# dc_sensor_v2.net
KiCad netlist of a schematic drawn in EAGLE
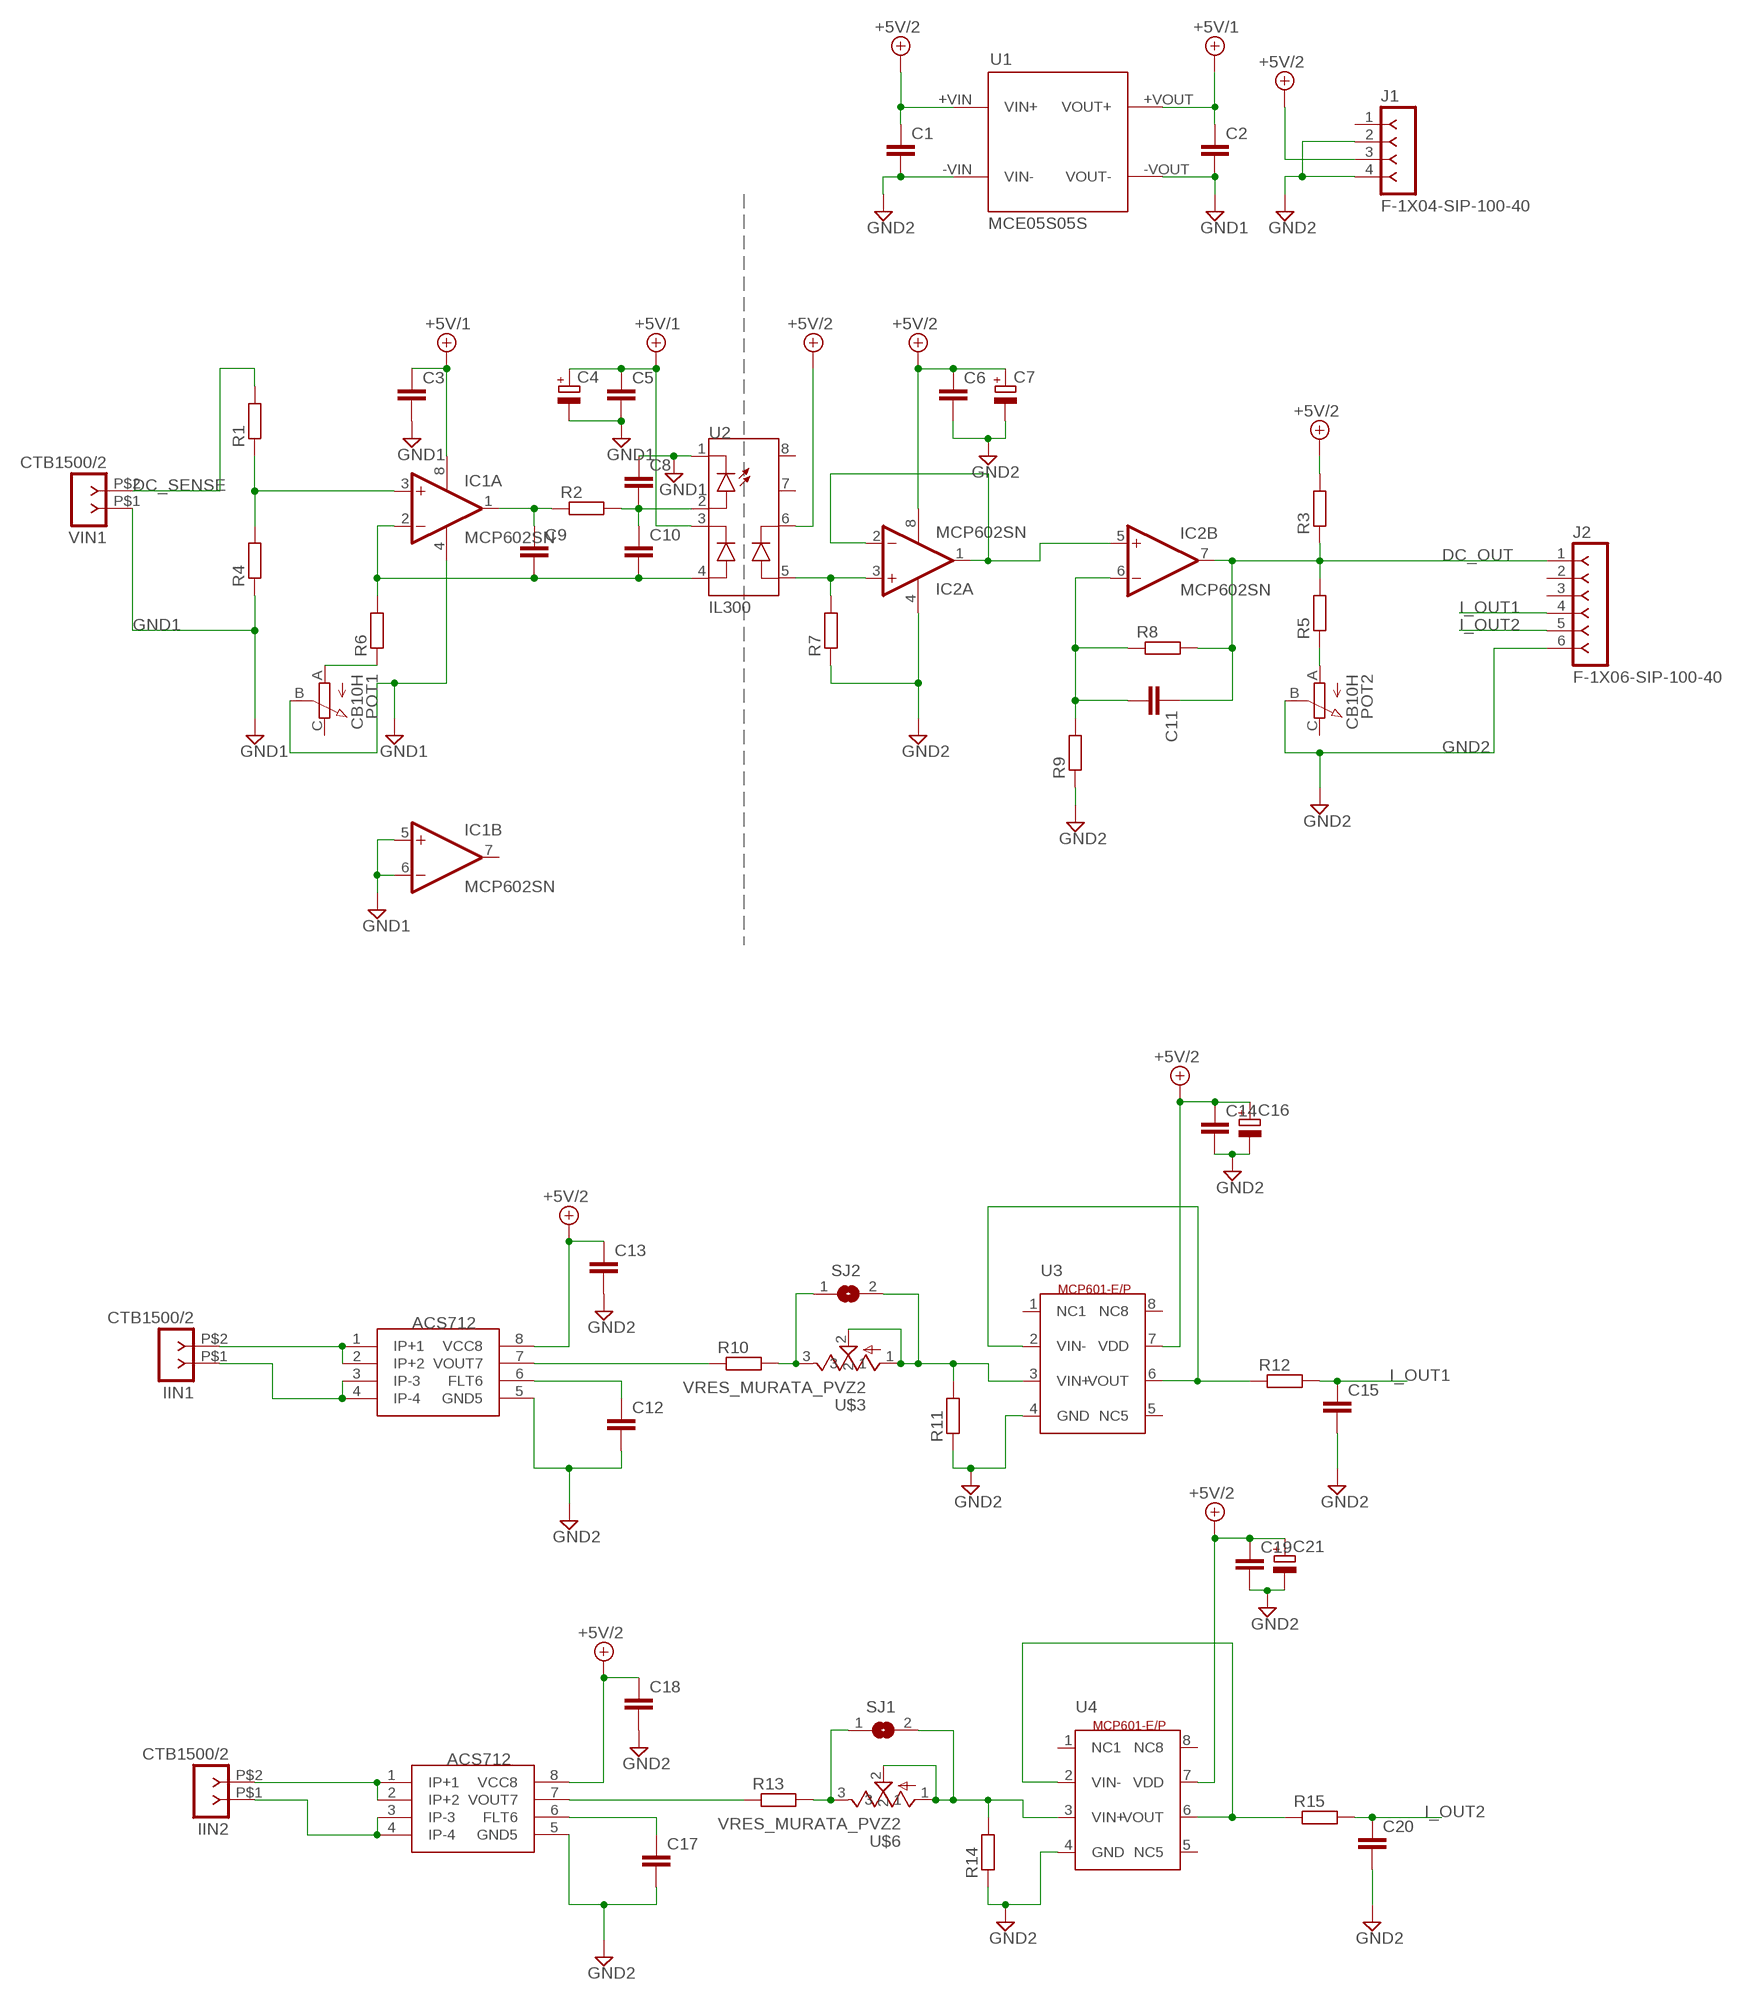
[diagram p0: schematic, sheet 1]

(export (version "E")
  (design (tool "Eeschema 10.0.6"))
  (components
    (comp (ref "C1")
      (value "C-EUC1206")
      (footprint "eagle-import:C1206")
      (libsource (lib "eagle-import") (part "C-EUC1206"))
    )
    (comp (ref "C2")
      (value "C-EUC1206")
      (footprint "eagle-import:C1206")
      (libsource (lib "eagle-import") (part "C-EUC1206"))
    )
    (comp (ref "C3")
      (value "C-EU025-040X050")
      (footprint "eagle-import:C025-040X050")
      (libsource (lib "eagle-import") (part "C-EU025-040X050"))
    )
    (comp (ref "C4")
      (value "CPOL-EUE2-5")
      (footprint "eagle-import:E2-5")
      (libsource (lib "eagle-import") (part "CPOL-EUE2-5"))
    )
    (comp (ref "C5")
      (value "C-EU025-040X050")
      (footprint "eagle-import:C025-040X050")
      (libsource (lib "eagle-import") (part "C-EU025-040X050"))
    )
    (comp (ref "C6")
      (value "C-EU025-040X050")
      (footprint "eagle-import:C025-040X050")
      (libsource (lib "eagle-import") (part "C-EU025-040X050"))
    )
    (comp (ref "C7")
      (value "CPOL-EUE2-5")
      (footprint "eagle-import:E2-5")
      (libsource (lib "eagle-import") (part "CPOL-EUE2-5"))
    )
    (comp (ref "C8")
      (value "C-EU025-040X050")
      (footprint "eagle-import:C025-040X050")
      (libsource (lib "eagle-import") (part "C-EU025-040X050"))
    )
    (comp (ref "C9")
      (value "C-EU025-040X050")
      (footprint "eagle-import:C025-040X050")
      (libsource (lib "eagle-import") (part "C-EU025-040X050"))
    )
    (comp (ref "C10")
      (value "C-EU025-040X050")
      (footprint "eagle-import:C025-040X050")
      (libsource (lib "eagle-import") (part "C-EU025-040X050"))
    )
    (comp (ref "C11")
      (value "C-EU025-040X050")
      (footprint "eagle-import:C025-040X050")
      (libsource (lib "eagle-import") (part "C-EU025-040X050"))
    )
    (comp (ref "C12")
      (value "C-EU025-030X050")
      (footprint "eagle-import:C025-030X050")
      (libsource (lib "eagle-import") (part "C-EU025-030X050"))
    )
    (comp (ref "C13")
      (value "C-EUC0603")
      (footprint "eagle-import:C0603")
      (libsource (lib "eagle-import") (part "C-EUC0603"))
    )
    (comp (ref "C14")
      (value "C-EUC0603")
      (footprint "eagle-import:C0603")
      (libsource (lib "eagle-import") (part "C-EUC0603"))
    )
    (comp (ref "C15")
      (value "C-EU025-030X050")
      (footprint "eagle-import:C025-030X050")
      (libsource (lib "eagle-import") (part "C-EU025-030X050"))
    )
    (comp (ref "C16")
      (value "CPOL-EUE2.5-6")
      (footprint "eagle-import:E2,5-6")
      (libsource (lib "eagle-import") (part "CPOL-EUE2.5-6"))
    )
    (comp (ref "C17")
      (value "C-EU025-030X050")
      (footprint "eagle-import:C025-030X050")
      (libsource (lib "eagle-import") (part "C-EU025-030X050"))
    )
    (comp (ref "C18")
      (value "C-EUC0603")
      (footprint "eagle-import:C0603")
      (libsource (lib "eagle-import") (part "C-EUC0603"))
    )
    (comp (ref "C19")
      (value "C-EUC0603")
      (footprint "eagle-import:C0603")
      (libsource (lib "eagle-import") (part "C-EUC0603"))
    )
    (comp (ref "C20")
      (value "C-EU025-030X050")
      (footprint "eagle-import:C025-030X050")
      (libsource (lib "eagle-import") (part "C-EU025-030X050"))
    )
    (comp (ref "C21")
      (value "CPOL-EUE2.5-6")
      (footprint "eagle-import:E2,5-6")
      (libsource (lib "eagle-import") (part "CPOL-EUE2.5-6"))
    )
    (comp (ref "IC1")
      (value "MCP602SN")
      (footprint "eagle-import:SO08")
      (libsource (lib "eagle-import") (part "MCP602SN"))
    )
    (comp (ref "IC2")
      (value "MCP602SN")
      (footprint "eagle-import:SO08")
      (libsource (lib "eagle-import") (part "MCP602SN"))
    )
    (comp (ref "IIN1")
      (value "CTB1500/2")
      (footprint "eagle-import:CTB1500-2")
      (libsource (lib "eagle-import") (part "CTB1500/2"))
    )
    (comp (ref "IIN2")
      (value "CTB1500/2")
      (footprint "eagle-import:CTB1500-2")
      (libsource (lib "eagle-import") (part "CTB1500/2"))
    )
    (comp (ref "J1")
      (value "F-1X04-SIP-100-40")
      (footprint "eagle-import:SIP-100-04-40")
      (libsource (lib "eagle-import") (part "F-1X04-SIP-100-40"))
    )
    (comp (ref "J2")
      (value "F-1X06-SIP-100-40")
      (footprint "eagle-import:SIP-100-06-40")
      (libsource (lib "eagle-import") (part "F-1X06-SIP-100-40"))
    )
    (comp (ref "POT1")
      (value "CB10H")
      (footprint "eagle-import:CB10V")
      (libsource (lib "eagle-import") (part "CB10H"))
    )
    (comp (ref "POT2")
      (value "CB10H")
      (footprint "eagle-import:CB10V")
      (libsource (lib "eagle-import") (part "CB10H"))
    )
    (comp (ref "R1")
      (value "R-EU_0207/10")
      (footprint "eagle-import:0207_10")
      (libsource (lib "eagle-import") (part "R-EU_0207/10"))
    )
    (comp (ref "R2")
      (value "R-EU_0207/10")
      (footprint "eagle-import:0207_10")
      (libsource (lib "eagle-import") (part "R-EU_0207/10"))
    )
    (comp (ref "R3")
      (value "R-EU_0207/10")
      (footprint "eagle-import:0207_10")
      (libsource (lib "eagle-import") (part "R-EU_0207/10"))
    )
    (comp (ref "R4")
      (value "R-EU_0207/10")
      (footprint "eagle-import:0207_10")
      (libsource (lib "eagle-import") (part "R-EU_0207/10"))
    )
    (comp (ref "R5")
      (value "R-EU_0207/10")
      (footprint "eagle-import:0207_10")
      (libsource (lib "eagle-import") (part "R-EU_0207/10"))
    )
    (comp (ref "R6")
      (value "R-EU_0207/10")
      (footprint "eagle-import:0207_10")
      (libsource (lib "eagle-import") (part "R-EU_0207/10"))
    )
    (comp (ref "R7")
      (value "R-EU_0207/10")
      (footprint "eagle-import:0207_10")
      (libsource (lib "eagle-import") (part "R-EU_0207/10"))
    )
    (comp (ref "R8")
      (value "R-EU_0207/10")
      (footprint "eagle-import:0207_10")
      (libsource (lib "eagle-import") (part "R-EU_0207/10"))
    )
    (comp (ref "R9")
      (value "R-EU_0207/10")
      (footprint "eagle-import:0207_10")
      (libsource (lib "eagle-import") (part "R-EU_0207/10"))
    )
    (comp (ref "R10")
      (value "R-EU_0207/10")
      (footprint "eagle-import:0207_10")
      (libsource (lib "eagle-import") (part "R-EU_0207/10"))
    )
    (comp (ref "R11")
      (value "R-EU_0207/10")
      (footprint "eagle-import:0207_10")
      (libsource (lib "eagle-import") (part "R-EU_0207/10"))
    )
    (comp (ref "R12")
      (value "R-EU_0207/10")
      (footprint "eagle-import:0207_10")
      (libsource (lib "eagle-import") (part "R-EU_0207/10"))
    )
    (comp (ref "R13")
      (value "R-EU_0207/10")
      (footprint "eagle-import:0207_10")
      (libsource (lib "eagle-import") (part "R-EU_0207/10"))
    )
    (comp (ref "R14")
      (value "R-EU_0207/10")
      (footprint "eagle-import:0207_10")
      (libsource (lib "eagle-import") (part "R-EU_0207/10"))
    )
    (comp (ref "R15")
      (value "R-EU_0207/10")
      (footprint "eagle-import:0207_10")
      (libsource (lib "eagle-import") (part "R-EU_0207/10"))
    )
    (comp (ref "SJ1") (value "SJ") (footprint "eagle-import:SJ") (libsource (lib "eagle-import") (part "SJ")))
    (comp (ref "SJ2") (value "SJ") (footprint "eagle-import:SJ") (libsource (lib "eagle-import") (part "SJ")))
    (comp (ref "U$3")
      (value "VRES_MURATA_PVZ2")
      (footprint "eagle-import:MURATA_PVZ2A")
      (libsource (lib "eagle-import") (part "VRES_MURATA_PVZ2"))
    )
    (comp (ref "U$6")
      (value "VRES_MURATA_PVZ2")
      (footprint "eagle-import:MURATA_PVZ2A")
      (libsource (lib "eagle-import") (part "VRES_MURATA_PVZ2"))
    )
    (comp (ref "U1")
      (value "MCE05S05S")
      (footprint "eagle-import:MCEXXSXXS_SIP")
      (libsource (lib "eagle-import") (part "MCE05S05S"))
    )
    (comp (ref "U2")
      (value "IL300")
      (footprint "eagle-import:DIL08")
      (libsource (lib "eagle-import") (part "IL300"))
    )
    (comp (ref "U3")
      (value "MCP601")
      (footprint "eagle-import:SO8")
      (libsource (lib "eagle-import") (part "MCP601"))
    )
    (comp (ref "U4")
      (value "MCP601")
      (footprint "eagle-import:SO8")
      (libsource (lib "eagle-import") (part "MCP601"))
    )
    (comp (ref "U5")
      (value "ACS712")
      (footprint "eagle-import:SO8")
      (libsource (lib "eagle-import") (part "ACS712"))
    )
    (comp (ref "U6")
      (value "ACS712")
      (footprint "eagle-import:SO8")
      (libsource (lib "eagle-import") (part "ACS712"))
    )
    (comp (ref "VIN1")
      (value "CTB1500/2")
      (footprint "eagle-import:CTB1500-2")
      (libsource (lib "eagle-import") (part "CTB1500/2"))
    )
  )
  (nets
    (net (code "1") (name "+5V{slash}1") (class "Default")
      (node (ref "C2") (pin "1") (pinfunction "1_1") (pintype "passive"))
      (node (ref "C3") (pin "1") (pinfunction "1_1") (pintype "passive"))
      (node (ref "C4") (pin "+") (pinfunction "+_+") (pintype "passive"))
      (node (ref "C5") (pin "1") (pinfunction "1_1") (pintype "passive"))
      (node (ref "IC1") (pin "8") (pinfunction "V+_8") (pintype "power_in"))
      (node (ref "U1") (pin "+VOUT") (pinfunction "VOUT+_+VOUT") (pintype "bidirectional"))
      (node (ref "U2") (pin "3") (pinfunction "C_FB_3") (pintype "passive"))
    )
    (net (code "2") (name "+5V{slash}2") (class "Default")
      (node (ref "C1") (pin "1") (pinfunction "1_1") (pintype "passive"))
      (node (ref "C13") (pin "1") (pinfunction "1_1") (pintype "passive"))
      (node (ref "C14") (pin "1") (pinfunction "1_1") (pintype "passive"))
      (node (ref "C16") (pin "+") (pinfunction "+_+") (pintype "passive"))
      (node (ref "C18") (pin "1") (pinfunction "1_1") (pintype "passive"))
      (node (ref "C19") (pin "1") (pinfunction "1_1") (pintype "passive"))
      (node (ref "C21") (pin "+") (pinfunction "+_+") (pintype "passive"))
      (node (ref "C6") (pin "1") (pinfunction "1_1") (pintype "passive"))
      (node (ref "C7") (pin "+") (pinfunction "+_+") (pintype "passive"))
      (node (ref "IC2") (pin "8") (pinfunction "V+_8") (pintype "power_in"))
      (node (ref "J1") (pin "3") (pinfunction "3_3") (pintype "passive"))
      (node (ref "R3") (pin "2") (pinfunction "2_2") (pintype "passive"))
      (node (ref "U1") (pin "+VIN") (pinfunction "VIN+_+VIN") (pintype "bidirectional"))
      (node (ref "U2") (pin "6") (pinfunction "C_OUT_6") (pintype "passive"))
      (node (ref "U3") (pin "7") (pinfunction "VDD_7") (pintype "power_in"))
      (node (ref "U4") (pin "7") (pinfunction "VDD_7") (pintype "power_in"))
      (node (ref "U5") (pin "8") (pinfunction "VCC8_8") (pintype "power_in"))
      (node (ref "U6") (pin "8") (pinfunction "VCC8_8") (pintype "power_in"))
    )
    (net (code "3") (name "/DC_OUT") (class "Default")
      (node (ref "C11") (pin "1") (pinfunction "1_1") (pintype "passive"))
      (node (ref "IC2") (pin "7") (pinfunction "OUT_7") (pintype "output"))
      (node (ref "J2") (pin "1") (pinfunction "1_1") (pintype "passive"))
      (node (ref "R3") (pin "1") (pinfunction "1_1") (pintype "passive"))
      (node (ref "R5") (pin "2") (pinfunction "2_2") (pintype "passive"))
      (node (ref "R8") (pin "2") (pinfunction "2_2") (pintype "passive"))
    )
    (net (code "4") (name "/DC_SENSE") (class "Default")
      (node (ref "R1") (pin "2") (pinfunction "2_2") (pintype "passive"))
      (node (ref "VIN1") (pin "P$2") (pinfunction "2_P$2") (pintype "passive"))
    )
    (net (code "5") (name "/I_OUT1") (class "Default")
      (node (ref "C15") (pin "1") (pinfunction "1_1") (pintype "passive"))
      (node (ref "J2") (pin "4") (pinfunction "4_4") (pintype "passive"))
      (node (ref "R12") (pin "2") (pinfunction "2_2") (pintype "passive"))
    )
    (net (code "6") (name "/I_OUT2") (class "Default")
      (node (ref "C20") (pin "1") (pinfunction "1_1") (pintype "passive"))
      (node (ref "J2") (pin "5") (pinfunction "5_5") (pintype "passive"))
      (node (ref "R15") (pin "2") (pinfunction "2_2") (pintype "passive"))
    )
    (net (code "7") (name "GND1") (class "Default")
      (node (ref "C2") (pin "2") (pinfunction "2_2") (pintype "passive"))
      (node (ref "C3") (pin "2") (pinfunction "2_2") (pintype "passive"))
      (node (ref "C4") (pin "-") (pinfunction "-_-") (pintype "passive"))
      (node (ref "C5") (pin "2") (pinfunction "2_2") (pintype "passive"))
      (node (ref "C8") (pin "1") (pinfunction "1_1") (pintype "passive"))
      (node (ref "IC1") (pin "4") (pinfunction "V-_4") (pintype "power_in"))
      (node (ref "IC1") (pin "5") (pinfunction "+IN_5") (pintype "input"))
      (node (ref "IC1") (pin "6") (pinfunction "-IN_6") (pintype "input"))
      (node (ref "POT1") (pin "B") (pinfunction "S_B") (pintype "passive"))
      (node (ref "R4") (pin "1") (pinfunction "1_1") (pintype "passive"))
      (node (ref "U1") (pin "-VOUT") (pinfunction "VOUT-_-VOUT") (pintype "bidirectional"))
      (node (ref "U2") (pin "1") (pinfunction "C_LED_1") (pintype "passive"))
      (node (ref "VIN1") (pin "P$1") (pinfunction "1_P$1") (pintype "passive"))
    )
    (net (code "8") (name "GND2") (class "Default")
      (node (ref "C1") (pin "2") (pinfunction "2_2") (pintype "passive"))
      (node (ref "C12") (pin "2") (pinfunction "2_2") (pintype "passive"))
      (node (ref "C13") (pin "2") (pinfunction "2_2") (pintype "passive"))
      (node (ref "C14") (pin "2") (pinfunction "2_2") (pintype "passive"))
      (node (ref "C15") (pin "2") (pinfunction "2_2") (pintype "passive"))
      (node (ref "C16") (pin "-") (pinfunction "-_-") (pintype "passive"))
      (node (ref "C17") (pin "2") (pinfunction "2_2") (pintype "passive"))
      (node (ref "C18") (pin "2") (pinfunction "2_2") (pintype "passive"))
      (node (ref "C19") (pin "2") (pinfunction "2_2") (pintype "passive"))
      (node (ref "C20") (pin "2") (pinfunction "2_2") (pintype "passive"))
      (node (ref "C21") (pin "-") (pinfunction "-_-") (pintype "passive"))
      (node (ref "C6") (pin "2") (pinfunction "2_2") (pintype "passive"))
      (node (ref "C7") (pin "-") (pinfunction "-_-") (pintype "passive"))
      (node (ref "IC2") (pin "4") (pinfunction "V-_4") (pintype "power_in"))
      (node (ref "J1") (pin "2") (pinfunction "2_2") (pintype "passive"))
      (node (ref "J1") (pin "4") (pinfunction "4_4") (pintype "passive"))
      (node (ref "J2") (pin "6") (pinfunction "6_6") (pintype "passive"))
      (node (ref "POT2") (pin "B") (pinfunction "S_B") (pintype "passive"))
      (node (ref "R11") (pin "1") (pinfunction "1_1") (pintype "passive"))
      (node (ref "R14") (pin "1") (pinfunction "1_1") (pintype "passive"))
      (node (ref "R7") (pin "1") (pinfunction "1_1") (pintype "passive"))
      (node (ref "R9") (pin "1") (pinfunction "1_1") (pintype "passive"))
      (node (ref "U1") (pin "-VIN") (pinfunction "VIN-_-VIN") (pintype "bidirectional"))
      (node (ref "U3") (pin "4") (pinfunction "GND_4") (pintype "power_in"))
      (node (ref "U4") (pin "4") (pinfunction "GND_4") (pintype "power_in"))
      (node (ref "U5") (pin "5") (pinfunction "GND5_5") (pintype "power_in"))
      (node (ref "U6") (pin "5") (pinfunction "GND5_5") (pintype "power_in"))
    )
    (net (code "9") (name "Net-(IC1A-+IN)") (class "Default")
      (node (ref "IC1") (pin "3") (pinfunction "+IN_3") (pintype "input"))
      (node (ref "R1") (pin "1") (pinfunction "1_1") (pintype "passive"))
      (node (ref "R4") (pin "2") (pinfunction "2_2") (pintype "passive"))
    )
    (net (code "10") (name "Net-(IC1A--IN)") (class "Default")
      (node (ref "C10") (pin "2") (pinfunction "2_2") (pintype "passive"))
      (node (ref "C9") (pin "2") (pinfunction "2_2") (pintype "passive"))
      (node (ref "IC1") (pin "2") (pinfunction "-IN_2") (pintype "input"))
      (node (ref "R6") (pin "2") (pinfunction "2_2") (pintype "passive"))
      (node (ref "U2") (pin "4") (pinfunction "A_FB_4") (pintype "passive"))
    )
    (net (code "11") (name "Net-(IC1A-OUT)") (class "Default")
      (node (ref "C9") (pin "1") (pinfunction "1_1") (pintype "passive"))
      (node (ref "IC1") (pin "1") (pinfunction "OUT_1") (pintype "output"))
      (node (ref "R2") (pin "1") (pinfunction "1_1") (pintype "passive"))
    )
    (net (code "12") (name "Net-(IC2A-+IN)") (class "Default")
      (node (ref "IC2") (pin "3") (pinfunction "+IN_3") (pintype "input"))
      (node (ref "R7") (pin "2") (pinfunction "2_2") (pintype "passive"))
      (node (ref "U2") (pin "5") (pinfunction "A_OUT_5") (pintype "passive"))
    )
    (net (code "13") (name "Net-(IC2A--IN)") (class "Default")
      (node (ref "IC2") (pin "1") (pinfunction "OUT_1") (pintype "output"))
      (node (ref "IC2") (pin "2") (pinfunction "-IN_2") (pintype "input"))
      (node (ref "IC2") (pin "5") (pinfunction "+IN_5") (pintype "input"))
    )
    (net (code "14") (name "Net-(IC2B--IN)") (class "Default")
      (node (ref "C11") (pin "2") (pinfunction "2_2") (pintype "passive"))
      (node (ref "IC2") (pin "6") (pinfunction "-IN_6") (pintype "input"))
      (node (ref "R8") (pin "1") (pinfunction "1_1") (pintype "passive"))
      (node (ref "R9") (pin "2") (pinfunction "2_2") (pintype "passive"))
    )
    (net (code "15") (name "Net-(IIN1-1)") (class "Default")
      (node (ref "IIN1") (pin "P$1") (pinfunction "1_P$1") (pintype "passive"))
      (node (ref "U6") (pin "3") (pinfunction "IP-3_3") (pintype "bidirectional"))
      (node (ref "U6") (pin "4") (pinfunction "IP-4_4") (pintype "bidirectional"))
    )
    (net (code "16") (name "Net-(IIN1-2)") (class "Default")
      (node (ref "IIN1") (pin "P$2") (pinfunction "2_P$2") (pintype "passive"))
      (node (ref "U6") (pin "1") (pinfunction "IP+1_1") (pintype "bidirectional"))
      (node (ref "U6") (pin "2") (pinfunction "IP+2_2") (pintype "bidirectional"))
    )
    (net (code "17") (name "Net-(IIN2-1)") (class "Default")
      (node (ref "IIN2") (pin "P$1") (pinfunction "1_P$1") (pintype "passive"))
      (node (ref "U5") (pin "3") (pinfunction "IP-3_3") (pintype "bidirectional"))
      (node (ref "U5") (pin "4") (pinfunction "IP-4_4") (pintype "bidirectional"))
    )
    (net (code "18") (name "Net-(IIN2-2)") (class "Default")
      (node (ref "IIN2") (pin "P$2") (pinfunction "2_P$2") (pintype "passive"))
      (node (ref "U5") (pin "1") (pinfunction "IP+1_1") (pintype "bidirectional"))
      (node (ref "U5") (pin "2") (pinfunction "IP+2_2") (pintype "bidirectional"))
    )
    (net (code "19") (name "Net-(POT1-PadA)") (class "Default")
      (node (ref "POT1") (pin "A") (pinfunction "A_A") (pintype "passive"))
      (node (ref "R6") (pin "1") (pinfunction "1_1") (pintype "passive"))
    )
    (net (code "20") (name "Net-(POT2-PadA)") (class "Default")
      (node (ref "POT2") (pin "A") (pinfunction "A_A") (pintype "passive"))
      (node (ref "R5") (pin "1") (pinfunction "1_1") (pintype "passive"))
    )
    (net (code "21") (name "Net-(R10-Pad2)") (class "Default")
      (node (ref "R10") (pin "2") (pinfunction "2_2") (pintype "passive"))
      (node (ref "SJ2") (pin "1") (pinfunction "1_1") (pintype "passive"))
      (node (ref "U$3") (pin "3") (pinfunction "3_3") (pintype "passive"))
    )
    (net (code "22") (name "Net-(R13-Pad2)") (class "Default")
      (node (ref "R13") (pin "2") (pinfunction "2_2") (pintype "passive"))
      (node (ref "SJ1") (pin "1") (pinfunction "1_1") (pintype "passive"))
      (node (ref "U$6") (pin "3") (pinfunction "3_3") (pintype "passive"))
    )
    (net (code "23") (name "Net-(U2-A_LED)") (class "Default")
      (node (ref "C10") (pin "1") (pinfunction "1_1") (pintype "passive"))
      (node (ref "C8") (pin "2") (pinfunction "2_2") (pintype "passive"))
      (node (ref "R2") (pin "2") (pinfunction "2_2") (pintype "passive"))
      (node (ref "U2") (pin "2") (pinfunction "A_LED_2") (pintype "passive"))
    )
    (net (code "24") (name "Net-(U3-VIN+)") (class "Default")
      (node (ref "R11") (pin "2") (pinfunction "2_2") (pintype "passive"))
      (node (ref "SJ2") (pin "2") (pinfunction "2_2") (pintype "passive"))
      (node (ref "U$3") (pin "1") (pinfunction "1_1") (pintype "passive"))
      (node (ref "U$3") (pin "2") (pinfunction "2_2") (pintype "passive"))
      (node (ref "U3") (pin "3") (pinfunction "VIN+_3") (pintype "bidirectional"))
    )
    (net (code "25") (name "Net-(U3-VIN-)") (class "Default")
      (node (ref "R12") (pin "1") (pinfunction "1_1") (pintype "passive"))
      (node (ref "U3") (pin "2") (pinfunction "VIN-_2") (pintype "bidirectional"))
      (node (ref "U3") (pin "6") (pinfunction "VOUT_6") (pintype "bidirectional"))
    )
    (net (code "26") (name "Net-(U4-VIN+)") (class "Default")
      (node (ref "R14") (pin "2") (pinfunction "2_2") (pintype "passive"))
      (node (ref "SJ1") (pin "2") (pinfunction "2_2") (pintype "passive"))
      (node (ref "U$6") (pin "1") (pinfunction "1_1") (pintype "passive"))
      (node (ref "U$6") (pin "2") (pinfunction "2_2") (pintype "passive"))
      (node (ref "U4") (pin "3") (pinfunction "VIN+_3") (pintype "bidirectional"))
    )
    (net (code "27") (name "Net-(U4-VIN-)") (class "Default")
      (node (ref "R15") (pin "1") (pinfunction "1_1") (pintype "passive"))
      (node (ref "U4") (pin "2") (pinfunction "VIN-_2") (pintype "bidirectional"))
      (node (ref "U4") (pin "6") (pinfunction "VOUT_6") (pintype "bidirectional"))
    )
    (net (code "28") (name "Net-(U5-FLT6)") (class "Default")
      (node (ref "C17") (pin "1") (pinfunction "1_1") (pintype "passive"))
      (node (ref "U5") (pin "6") (pinfunction "FLT6_6") (pintype "passive"))
    )
    (net (code "29") (name "Net-(U5-VOUT7)") (class "Default")
      (node (ref "R13") (pin "1") (pinfunction "1_1") (pintype "passive"))
      (node (ref "U5") (pin "7") (pinfunction "VOUT7_7") (pintype "output"))
    )
    (net (code "30") (name "Net-(U6-FLT6)") (class "Default")
      (node (ref "C12") (pin "1") (pinfunction "1_1") (pintype "passive"))
      (node (ref "U6") (pin "6") (pinfunction "FLT6_6") (pintype "passive"))
    )
    (net (code "31") (name "Net-(U6-VOUT7)") (class "Default")
      (node (ref "R10") (pin "1") (pinfunction "1_1") (pintype "passive"))
      (node (ref "U6") (pin "7") (pinfunction "VOUT7_7") (pintype "output"))
    )
    (net (code "32") (name "unconnected-(IC1B-OUT-Pad7)") (class "Default")
      (node (ref "IC1") (pin "7") (pinfunction "OUT_7") (pintype "output"))
    )
    (net (code "33") (name "unconnected-(J1-Pad1)") (class "Default")
      (node (ref "J1") (pin "1") (pinfunction "1_1") (pintype "passive"))
    )
    (net (code "34") (name "unconnected-(J2-Pad2)") (class "Default")
      (node (ref "J2") (pin "2") (pinfunction "2_2") (pintype "passive"))
    )
    (net (code "35") (name "unconnected-(J2-Pad3)") (class "Default")
      (node (ref "J2") (pin "3") (pinfunction "3_3") (pintype "passive"))
    )
    (net (code "36") (name "unconnected-(POT1-E-PadC)") (class "Default")
      (node (ref "POT1") (pin "C") (pinfunction "E_C") (pintype "passive"))
    )
    (net (code "37") (name "unconnected-(POT2-E-PadC)") (class "Default")
      (node (ref "POT2") (pin "C") (pinfunction "E_C") (pintype "passive"))
    )
    (net (code "38") (name "unconnected-(U2-PIN7-Pad7)") (class "Default")
      (node (ref "U2") (pin "7") (pinfunction "PIN7_7") (pintype "no_connect"))
    )
    (net (code "39") (name "unconnected-(U2-PIN8-Pad8)") (class "Default")
      (node (ref "U2") (pin "8") (pinfunction "PIN8_8") (pintype "no_connect"))
    )
    (net (code "40") (name "unconnected-(U3-NC1-Pad1)") (class "Default")
      (node (ref "U3") (pin "1") (pinfunction "NC1_1") (pintype "no_connect"))
    )
    (net (code "41") (name "unconnected-(U3-NC5-Pad5)") (class "Default")
      (node (ref "U3") (pin "5") (pinfunction "NC5_5") (pintype "no_connect"))
    )
    (net (code "42") (name "unconnected-(U3-NC8-Pad8)") (class "Default")
      (node (ref "U3") (pin "8") (pinfunction "NC8_8") (pintype "no_connect"))
    )
    (net (code "43") (name "unconnected-(U4-NC1-Pad1)") (class "Default")
      (node (ref "U4") (pin "1") (pinfunction "NC1_1") (pintype "no_connect"))
    )
    (net (code "44") (name "unconnected-(U4-NC5-Pad5)") (class "Default")
      (node (ref "U4") (pin "5") (pinfunction "NC5_5") (pintype "no_connect"))
    )
    (net (code "45") (name "unconnected-(U4-NC8-Pad8)") (class "Default")
      (node (ref "U4") (pin "8") (pinfunction "NC8_8") (pintype "no_connect"))
    )
  )
)
